# SW_PB_SPNOx5_SMD.net
KiCad netlist of a schematic drawn in Altium Designer
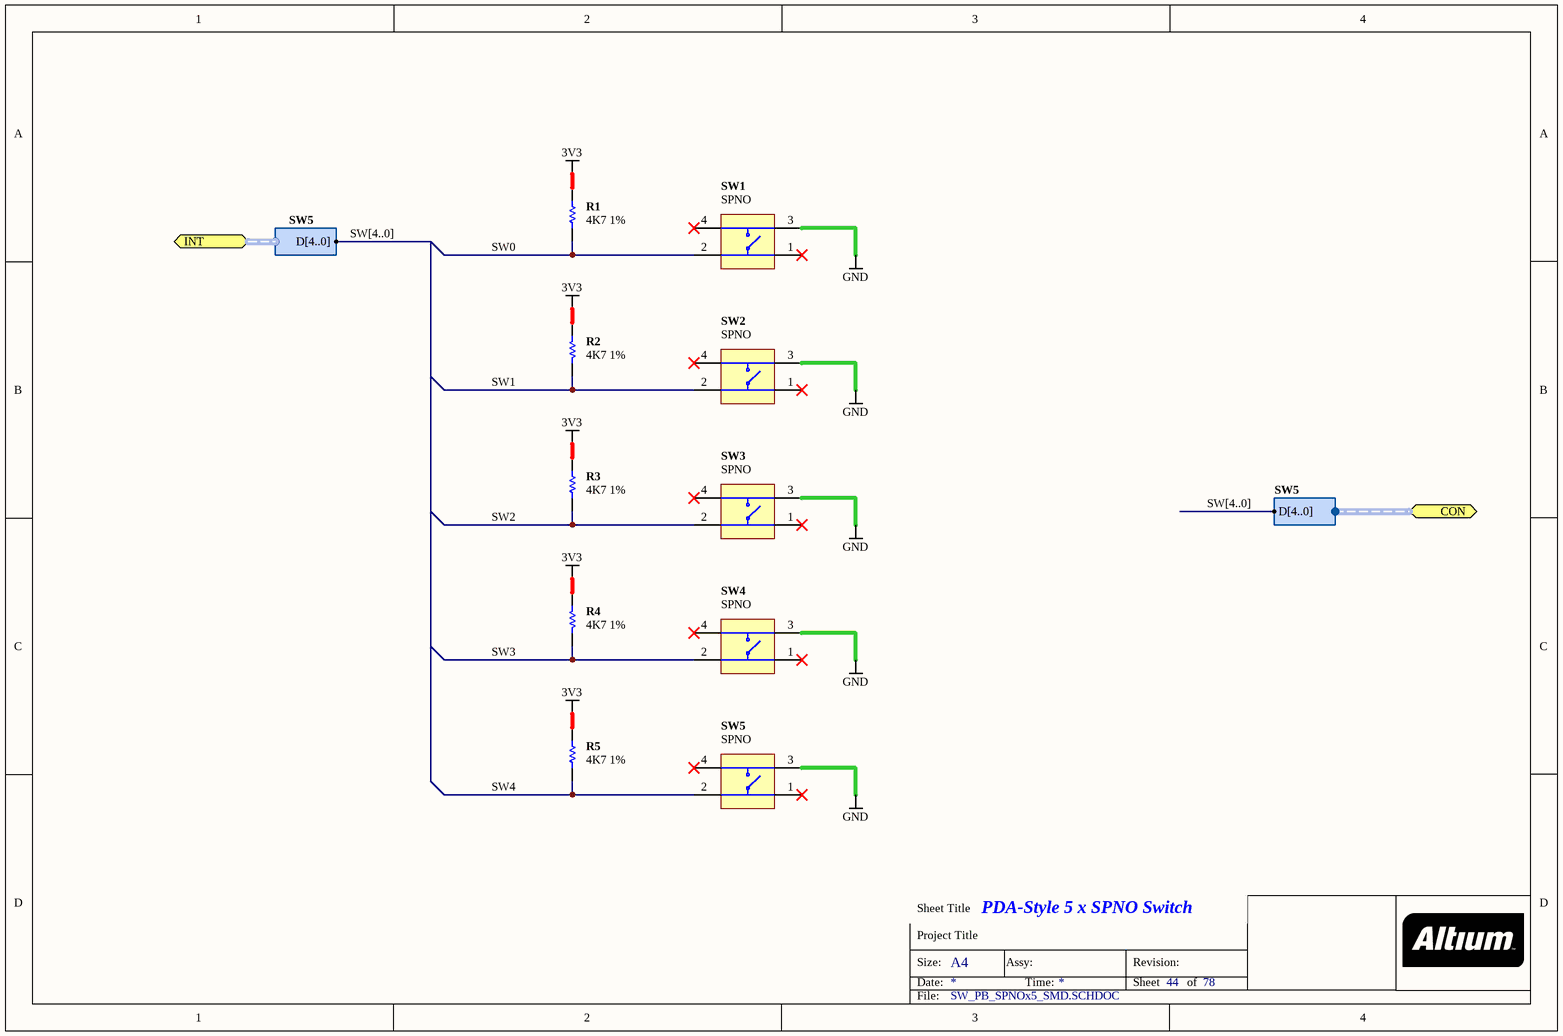
[diagram p0: SW_PB_SPNOx5_SMD.SCHDOC]

(export (version "E")
  (design (tool "Eeschema 10.0.6"))
  (components
    (comp (ref "R1")
      (value "4K7 1%")
      (footprint "RESC1005-STAR")
      (description "Resistor, 4K7 1% 0402 (1005)")
      (fields (field (name "TOLERANCE") "1 %"))
      (libsource (lib "altium-import") (part "root_0_RES_"))
    )
    (comp (ref "R2")
      (value "4K7 1%")
      (footprint "RESC1005-STAR")
      (description "Resistor, 4K7 1% 0402 (1005)")
      (fields (field (name "TOLERANCE") "1 %"))
      (libsource (lib "altium-import") (part "root_0_mirrored_RES_"))
    )
    (comp (ref "R3")
      (value "4K7 1%")
      (footprint "RESC1005-STAR")
      (description "Resistor, 4K7 1% 0402 (1005)")
      (fields (field (name "TOLERANCE") "1 %"))
      (libsource (lib "altium-import") (part "root_2_RES_"))
    )
    (comp (ref "R4")
      (value "4K7 1%")
      (footprint "RESC1005-STAR")
      (description "Resistor, 4K7 1% 0402 (1005)")
      (fields (field (name "TOLERANCE") "1 %"))
      (libsource (lib "altium-import") (part "root_0_mirrored_RES_"))
    )
    (comp (ref "R5")
      (value "4K7 1%")
      (footprint "RESC1005-STAR")
      (description "Resistor, 4K7 1% 0402 (1005)")
      (fields (field (name "TOLERANCE") "1 %"))
      (libsource (lib "altium-import") (part "root_2_RES_"))
    )
    (comp (ref "SW1")
      (value "SPNO")
      (footprint "SW_DTSM-61NT/R")
      (description "Switch, SPNO Push Button SMD")
      (libsource (lib "AltiumDesignLibrary") (part "SWI-PB-SPNO"))
    )
    (comp (ref "SW2")
      (value "SPNO")
      (footprint "SW_DTSM-61NT/R")
      (description "Switch, SPNO Push Button SMD")
      (libsource (lib "AltiumDesignLibrary") (part "SWI-PB-SPNO"))
    )
    (comp (ref "SW3")
      (value "SPNO")
      (footprint "SW_DTSM-61NT/R")
      (description "Switch, SPNO Push Button SMD")
      (libsource (lib "AltiumDesignLibrary") (part "SWI-PB-SPNO"))
    )
    (comp (ref "SW4")
      (value "SPNO")
      (footprint "SW_DTSM-61NT/R")
      (description "Switch, SPNO Push Button SMD")
      (libsource (lib "AltiumDesignLibrary") (part "SWI-PB-SPNO"))
    )
    (comp (ref "SW5")
      (value "SPNO")
      (footprint "SW_DTSM-61NT/R")
      (description "Switch, SPNO Push Button SMD")
      (libsource (lib "AltiumDesignLibrary") (part "SWI-PB-SPNO"))
    )
  )
  (nets
    (net (code "4") (name "/SW0") (class "Default")
      (node (ref "R1") (pin "2") (pinfunction "2_2") (pintype "passive"))
      (node (ref "SW1") (pin "2") (pinfunction "2_2") (pintype "passive"))
    )
    (net (code "5") (name "/SW1") (class "Default")
      (node (ref "R2") (pin "2") (pinfunction "2_2") (pintype "passive"))
      (node (ref "SW2") (pin "2") (pinfunction "2_2") (pintype "passive"))
    )
    (net (code "6") (name "/SW2") (class "Default")
      (node (ref "R3") (pin "1") (pinfunction "1_1") (pintype "passive"))
      (node (ref "SW3") (pin "2") (pinfunction "2_2") (pintype "passive"))
    )
    (net (code "7") (name "/SW3") (class "Default")
      (node (ref "R4") (pin "2") (pinfunction "2_2") (pintype "passive"))
      (node (ref "SW4") (pin "2") (pinfunction "2_2") (pintype "passive"))
    )
    (net (code "8") (name "/SW4") (class "Default")
      (node (ref "R5") (pin "1") (pinfunction "1_1") (pintype "passive"))
      (node (ref "SW5") (pin "2") (pinfunction "2_2") (pintype "passive"))
    )
    (net (code "12") (name "3V3") (class "Default")
      (node (ref "R1") (pin "1") (pinfunction "1_1") (pintype "passive"))
      (node (ref "R2") (pin "1") (pinfunction "1_1") (pintype "passive"))
      (node (ref "R3") (pin "2") (pinfunction "2_2") (pintype "passive"))
      (node (ref "R4") (pin "1") (pinfunction "1_1") (pintype "passive"))
      (node (ref "R5") (pin "2") (pinfunction "2_2") (pintype "passive"))
    )
    (net (code "13") (name "GND") (class "Default")
      (node (ref "SW1") (pin "3") (pinfunction "3_3") (pintype "passive"))
      (node (ref "SW2") (pin "3") (pinfunction "3_3") (pintype "passive"))
      (node (ref "SW3") (pin "3") (pinfunction "3_3") (pintype "passive"))
      (node (ref "SW4") (pin "3") (pinfunction "3_3") (pintype "passive"))
      (node (ref "SW5") (pin "3") (pinfunction "3_3") (pintype "passive"))
    )
    (net (code "14") (name "unconnected-(SW1-Pad1)") (class "Default")
      (node (ref "SW1") (pin "1") (pinfunction "1_1") (pintype "passive+no_connect"))
    )
    (net (code "15") (name "unconnected-(SW1-Pad4)") (class "Default")
      (node (ref "SW1") (pin "4") (pinfunction "4_4") (pintype "passive+no_connect"))
    )
    (net (code "16") (name "unconnected-(SW2-Pad1)") (class "Default")
      (node (ref "SW2") (pin "1") (pinfunction "1_1") (pintype "passive+no_connect"))
    )
    (net (code "17") (name "unconnected-(SW2-Pad4)") (class "Default")
      (node (ref "SW2") (pin "4") (pinfunction "4_4") (pintype "passive+no_connect"))
    )
    (net (code "18") (name "unconnected-(SW3-Pad1)") (class "Default")
      (node (ref "SW3") (pin "1") (pinfunction "1_1") (pintype "passive+no_connect"))
    )
    (net (code "19") (name "unconnected-(SW3-Pad4)") (class "Default")
      (node (ref "SW3") (pin "4") (pinfunction "4_4") (pintype "passive+no_connect"))
    )
    (net (code "20") (name "unconnected-(SW4-Pad1)") (class "Default")
      (node (ref "SW4") (pin "1") (pinfunction "1_1") (pintype "passive+no_connect"))
    )
    (net (code "21") (name "unconnected-(SW4-Pad4)") (class "Default")
      (node (ref "SW4") (pin "4") (pinfunction "4_4") (pintype "passive+no_connect"))
    )
    (net (code "22") (name "unconnected-(SW5-Pad1)") (class "Default")
      (node (ref "SW5") (pin "1") (pinfunction "1_1") (pintype "passive+no_connect"))
    )
    (net (code "23") (name "unconnected-(SW5-Pad4)") (class "Default")
      (node (ref "SW5") (pin "4") (pinfunction "4_4") (pintype "passive+no_connect"))
    )
  )
)
